# Benes_bel.net
KiCad netlist of a schematic drawn in EAGLE
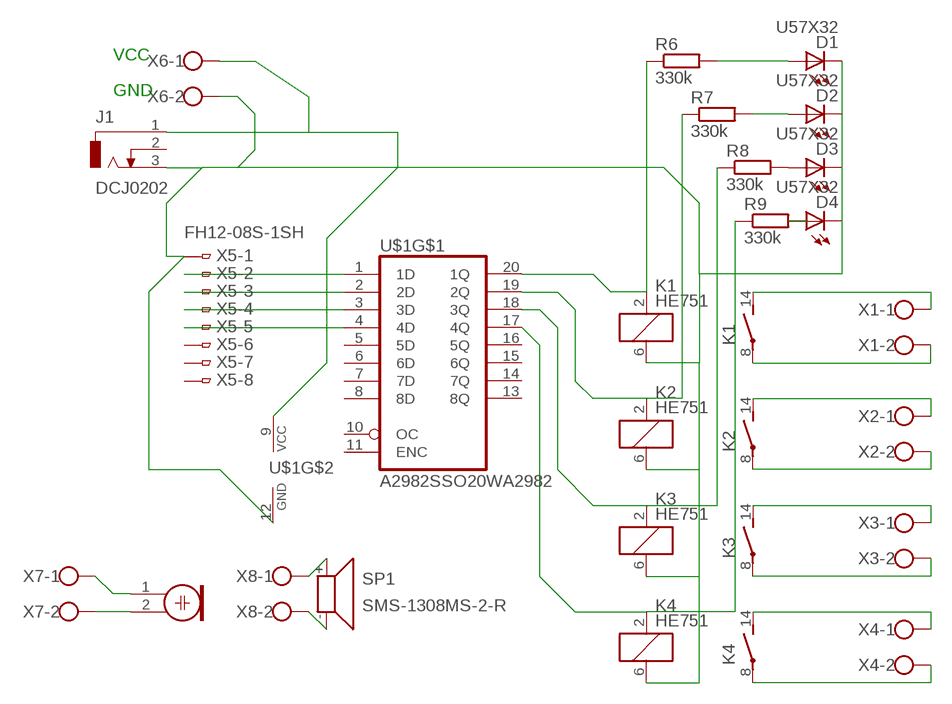
[diagram p0: schematic, sheet 1]

(export (version "E")
  (design (tool "Eeschema 10.0.6"))
  (components
    (comp (ref "D1")
      (value "U57X32")
      (footprint "eagle-import:U57X32")
      (libsource (lib "eagle-import") (part "U57X32"))
    )
    (comp (ref "D2")
      (value "U57X32")
      (footprint "eagle-import:U57X32")
      (libsource (lib "eagle-import") (part "U57X32"))
    )
    (comp (ref "D3")
      (value "U57X32")
      (footprint "eagle-import:U57X32")
      (libsource (lib "eagle-import") (part "U57X32"))
    )
    (comp (ref "D4")
      (value "U57X32")
      (footprint "eagle-import:U57X32")
      (libsource (lib "eagle-import") (part "U57X32"))
    )
    (comp (ref "J1")
      (value "DCJ0202")
      (footprint "eagle-import:DCJ0202")
      (libsource (lib "eagle-import") (part "DCJ0202"))
    )
    (comp (ref "K1")
      (value "HE751")
      (footprint "eagle-import:HE751")
      (libsource (lib "eagle-import") (part "HE751"))
    )
    (comp (ref "K2")
      (value "HE751")
      (footprint "eagle-import:HE751")
      (libsource (lib "eagle-import") (part "HE751"))
    )
    (comp (ref "K3")
      (value "HE751")
      (footprint "eagle-import:HE751")
      (libsource (lib "eagle-import") (part "HE751"))
    )
    (comp (ref "K4")
      (value "HE751")
      (footprint "eagle-import:HE751")
      (libsource (lib "eagle-import") (part "HE751"))
    )
    (comp (ref "M1")
      (value "ELECTRET_MICROPHON-WM-61B")
      (footprint "eagle-import:WM-61B")
      (libsource (lib "eagle-import") (part "ELECTRET_MICROPHON-WM-61B"))
    )
    (comp (ref "R6")
      (value "330k")
      (footprint "eagle-import:0207_12")
      (libsource (lib "eagle-import") (part "R-EU_0207/12"))
    )
    (comp (ref "R7")
      (value "330k")
      (footprint "eagle-import:0207_12")
      (libsource (lib "eagle-import") (part "R-EU_0207/12"))
    )
    (comp (ref "R8")
      (value "330k")
      (footprint "eagle-import:0207_12")
      (libsource (lib "eagle-import") (part "R-EU_0207/12"))
    )
    (comp (ref "R9")
      (value "330k")
      (footprint "eagle-import:0207_12")
      (libsource (lib "eagle-import") (part "R-EU_0207/12"))
    )
    (comp (ref "SP1")
      (value "SMS-1308MS-2-R")
      (footprint "eagle-import:SMS-1308MS-2-R")
      (libsource (lib "eagle-import") (part "SMS-1308MS-2-R"))
    )
    (comp (ref "U$1")
      (value "A2982SSO20WA2982")
      (footprint "eagle-import:SO20W")
      (libsource (lib "eagle-import") (part "A2982SSO20WA2982"))
    )
    (comp (ref "X1")
      (value "W237-102")
      (footprint "eagle-import:W237-102")
      (fields (field (name "MPN") "237-102"))
      (libsource (lib "eagle-import") (part "W237-102"))
    )
    (comp (ref "X2")
      (value "W237-102")
      (footprint "eagle-import:W237-102")
      (fields (field (name "MPN") "237-102"))
      (libsource (lib "eagle-import") (part "W237-102"))
    )
    (comp (ref "X3")
      (value "W237-102")
      (footprint "eagle-import:W237-102")
      (fields (field (name "MPN") "237-102"))
      (libsource (lib "eagle-import") (part "W237-102"))
    )
    (comp (ref "X4")
      (value "W237-102")
      (footprint "eagle-import:W237-102")
      (fields (field (name "MPN") "237-102"))
      (libsource (lib "eagle-import") (part "W237-102"))
    )
    (comp (ref "X5")
      (value "FH12-08S-1SH")
      (footprint "eagle-import:FH12-08S-1SH")
      (libsource (lib "eagle-import") (part "FH12-08S-1SH"))
    )
    (comp (ref "X6")
      (value "W237-102")
      (footprint "eagle-import:W237-102")
      (fields (field (name "MPN") "237-102"))
      (libsource (lib "eagle-import") (part "W237-102"))
    )
    (comp (ref "X7")
      (value "W237-102")
      (footprint "eagle-import:W237-102")
      (fields (field (name "MPN") "237-102"))
      (libsource (lib "eagle-import") (part "W237-102"))
    )
    (comp (ref "X8")
      (value "W237-102")
      (footprint "eagle-import:W237-102")
      (fields (field (name "MPN") "237-102"))
      (libsource (lib "eagle-import") (part "W237-102"))
    )
  )
  (nets
    (net (code "1") (name "Net-(D1-C)") (class "Default")
      (node (ref "D1") (pin "K") (pinfunction "C_K") (pintype "passive"))
      (node (ref "D2") (pin "K") (pinfunction "C_K") (pintype "passive"))
      (node (ref "D3") (pin "K") (pinfunction "C_K") (pintype "passive"))
      (node (ref "D4") (pin "K") (pinfunction "C_K") (pintype "passive"))
      (node (ref "J1") (pin "3") (pinfunction "3_3") (pintype "passive"))
      (node (ref "K1") (pin "6") (pinfunction "2_6") (pintype "passive"))
      (node (ref "K2") (pin "6") (pinfunction "2_6") (pintype "passive"))
      (node (ref "K3") (pin "6") (pinfunction "2_6") (pintype "passive"))
      (node (ref "K4") (pin "6") (pinfunction "2_6") (pintype "passive"))
      (node (ref "U$1") (pin "12") (pinfunction "GND_12") (pintype "power_in"))
      (node (ref "X5") (pin "1") (pinfunction "1_1") (pintype "passive"))
      (node (ref "X6") (pin "2") (pinfunction "KL_2") (pintype "passive"))
    )
    (net (code "2") (name "Net-(D1-PadA)") (class "Default")
      (node (ref "D1") (pin "A") (pinfunction "A_A") (pintype "passive"))
      (node (ref "R6") (pin "2") (pinfunction "2_2") (pintype "passive"))
    )
    (net (code "3") (name "Net-(D2-PadA)") (class "Default")
      (node (ref "D2") (pin "A") (pinfunction "A_A") (pintype "passive"))
      (node (ref "R7") (pin "2") (pinfunction "2_2") (pintype "passive"))
    )
    (net (code "4") (name "Net-(D3-PadA)") (class "Default")
      (node (ref "D3") (pin "A") (pinfunction "A_A") (pintype "passive"))
      (node (ref "R8") (pin "2") (pinfunction "2_2") (pintype "passive"))
    )
    (net (code "5") (name "Net-(D4-PadA)") (class "Default")
      (node (ref "D4") (pin "A") (pinfunction "A_A") (pintype "passive"))
      (node (ref "R9") (pin "2") (pinfunction "2_2") (pintype "passive"))
    )
    (net (code "6") (name "Net-(K1A-1)") (class "Default")
      (node (ref "K1") (pin "2") (pinfunction "1_2") (pintype "passive"))
      (node (ref "R6") (pin "1") (pinfunction "1_1") (pintype "passive"))
      (node (ref "U$1") (pin "20") (pinfunction "1Q_20") (pintype "tri_state"))
    )
    (net (code "7") (name "Net-(K1B-P)") (class "Default")
      (node (ref "K1") (pin "8") (pinfunction "P_8") (pintype "passive"))
      (node (ref "X1") (pin "2") (pinfunction "KL_2") (pintype "passive"))
    )
    (net (code "8") (name "Net-(K1B-S)") (class "Default")
      (node (ref "K1") (pin "14") (pinfunction "S_14") (pintype "passive"))
      (node (ref "X1") (pin "1") (pinfunction "KL_1") (pintype "passive"))
    )
    (net (code "9") (name "Net-(K2A-1)") (class "Default")
      (node (ref "K2") (pin "2") (pinfunction "1_2") (pintype "passive"))
      (node (ref "R7") (pin "1") (pinfunction "1_1") (pintype "passive"))
      (node (ref "U$1") (pin "19") (pinfunction "2Q_19") (pintype "tri_state"))
    )
    (net (code "10") (name "Net-(K2B-P)") (class "Default")
      (node (ref "K2") (pin "8") (pinfunction "P_8") (pintype "passive"))
      (node (ref "X2") (pin "2") (pinfunction "KL_2") (pintype "passive"))
    )
    (net (code "11") (name "Net-(K2B-S)") (class "Default")
      (node (ref "K2") (pin "14") (pinfunction "S_14") (pintype "passive"))
      (node (ref "X2") (pin "1") (pinfunction "KL_1") (pintype "passive"))
    )
    (net (code "12") (name "Net-(K3A-1)") (class "Default")
      (node (ref "K3") (pin "2") (pinfunction "1_2") (pintype "passive"))
      (node (ref "R8") (pin "1") (pinfunction "1_1") (pintype "passive"))
      (node (ref "U$1") (pin "18") (pinfunction "3Q_18") (pintype "tri_state"))
    )
    (net (code "13") (name "Net-(K3B-P)") (class "Default")
      (node (ref "K3") (pin "8") (pinfunction "P_8") (pintype "passive"))
      (node (ref "X3") (pin "2") (pinfunction "KL_2") (pintype "passive"))
    )
    (net (code "14") (name "Net-(K3B-S)") (class "Default")
      (node (ref "K3") (pin "14") (pinfunction "S_14") (pintype "passive"))
      (node (ref "X3") (pin "1") (pinfunction "KL_1") (pintype "passive"))
    )
    (net (code "15") (name "Net-(K4A-1)") (class "Default")
      (node (ref "K4") (pin "2") (pinfunction "1_2") (pintype "passive"))
      (node (ref "R9") (pin "1") (pinfunction "1_1") (pintype "passive"))
      (node (ref "U$1") (pin "17") (pinfunction "4Q_17") (pintype "tri_state"))
    )
    (net (code "16") (name "Net-(K4B-P)") (class "Default")
      (node (ref "K4") (pin "8") (pinfunction "P_8") (pintype "passive"))
      (node (ref "X4") (pin "2") (pinfunction "KL_2") (pintype "passive"))
    )
    (net (code "17") (name "Net-(K4B-S)") (class "Default")
      (node (ref "K4") (pin "14") (pinfunction "S_14") (pintype "passive"))
      (node (ref "X4") (pin "1") (pinfunction "KL_1") (pintype "passive"))
    )
    (net (code "18") (name "Net-(SP1-1)") (class "Default")
      (node (ref "SP1") (pin "+") (pinfunction "1_+") (pintype "passive"))
      (node (ref "X8") (pin "1") (pinfunction "KL_1") (pintype "passive"))
    )
    (net (code "19") (name "Net-(SP1-2)") (class "Default")
      (node (ref "SP1") (pin "-") (pinfunction "2_-") (pintype "passive"))
      (node (ref "X8") (pin "2") (pinfunction "KL_2") (pintype "passive"))
    )
    (net (code "20") (name "Net-(U$1A-1D)") (class "Default")
      (node (ref "U$1") (pin "1") (pinfunction "1D_1") (pintype "input"))
      (node (ref "X5") (pin "2") (pinfunction "1_2") (pintype "passive"))
    )
    (net (code "21") (name "Net-(U$1A-2D)") (class "Default")
      (node (ref "U$1") (pin "2") (pinfunction "2D_2") (pintype "input"))
      (node (ref "X5") (pin "3") (pinfunction "1_3") (pintype "passive"))
    )
    (net (code "22") (name "Net-(U$1A-3D)") (class "Default")
      (node (ref "U$1") (pin "3") (pinfunction "3D_3") (pintype "input"))
      (node (ref "X5") (pin "4") (pinfunction "1_4") (pintype "passive"))
    )
    (net (code "23") (name "Net-(U$1A-4D)") (class "Default")
      (node (ref "U$1") (pin "4") (pinfunction "4D_4") (pintype "input"))
      (node (ref "X5") (pin "5") (pinfunction "1_5") (pintype "passive"))
    )
    (net (code "24") (name "Net-(U$1B-VCC)") (class "Default")
      (node (ref "J1") (pin "1") (pinfunction "1_1") (pintype "passive"))
      (node (ref "U$1") (pin "9") (pinfunction "VCC_9") (pintype "power_in"))
      (node (ref "X6") (pin "1") (pinfunction "KL_1") (pintype "passive"))
    )
    (net (code "25") (name "Net-(X7A-KL)") (class "Default")
      (node (ref "M1") (pin "1") (pinfunction "1_1") (pintype "passive"))
      (node (ref "X7") (pin "1") (pinfunction "KL_1") (pintype "passive"))
    )
    (net (code "26") (name "Net-(X7B-KL)") (class "Default")
      (node (ref "M1") (pin "2") (pinfunction "2_2") (pintype "passive"))
      (node (ref "X7") (pin "2") (pinfunction "KL_2") (pintype "passive"))
    )
    (net (code "27") (name "unconnected-(J1-Pad2)") (class "Default")
      (node (ref "J1") (pin "2") (pinfunction "2_2") (pintype "passive"))
    )
    (net (code "28") (name "unconnected-(U$1A-5D-Pad5)") (class "Default")
      (node (ref "U$1") (pin "5") (pinfunction "5D_5") (pintype "input"))
    )
    (net (code "29") (name "unconnected-(U$1A-5Q-Pad16)") (class "Default")
      (node (ref "U$1") (pin "16") (pinfunction "5Q_16") (pintype "tri_state"))
    )
    (net (code "30") (name "unconnected-(U$1A-6D-Pad6)") (class "Default")
      (node (ref "U$1") (pin "6") (pinfunction "6D_6") (pintype "input"))
    )
    (net (code "31") (name "unconnected-(U$1A-6Q-Pad15)") (class "Default")
      (node (ref "U$1") (pin "15") (pinfunction "6Q_15") (pintype "tri_state"))
    )
    (net (code "32") (name "unconnected-(U$1A-7D-Pad7)") (class "Default")
      (node (ref "U$1") (pin "7") (pinfunction "7D_7") (pintype "input"))
    )
    (net (code "33") (name "unconnected-(U$1A-7Q-Pad14)") (class "Default")
      (node (ref "U$1") (pin "14") (pinfunction "7Q_14") (pintype "tri_state"))
    )
    (net (code "34") (name "unconnected-(U$1A-8D-Pad8)") (class "Default")
      (node (ref "U$1") (pin "8") (pinfunction "8D_8") (pintype "input"))
    )
    (net (code "35") (name "unconnected-(U$1A-8Q-Pad13)") (class "Default")
      (node (ref "U$1") (pin "13") (pinfunction "8Q_13") (pintype "tri_state"))
    )
    (net (code "36") (name "unconnected-(U$1A-ENC-Pad11)") (class "Default")
      (node (ref "U$1") (pin "11") (pinfunction "ENC_11") (pintype "input"))
    )
    (net (code "37") (name "unconnected-(U$1A-OC-Pad10)") (class "Default")
      (node (ref "U$1") (pin "10") (pinfunction "OC_10") (pintype "input"))
    )
    (net (code "38") (name "unconnected-(X5F-1-Pad6)") (class "Default")
      (node (ref "X5") (pin "6") (pinfunction "1_6") (pintype "passive"))
    )
    (net (code "39") (name "unconnected-(X5G-1-Pad7)") (class "Default")
      (node (ref "X5") (pin "7") (pinfunction "1_7") (pintype "passive"))
    )
    (net (code "40") (name "unconnected-(X5H-1-Pad8)") (class "Default")
      (node (ref "X5") (pin "8") (pinfunction "1_8") (pintype "passive"))
    )
  )
)
